# 09_Ethernet.net
KiCad netlist of a schematic drawn in Altium Designer
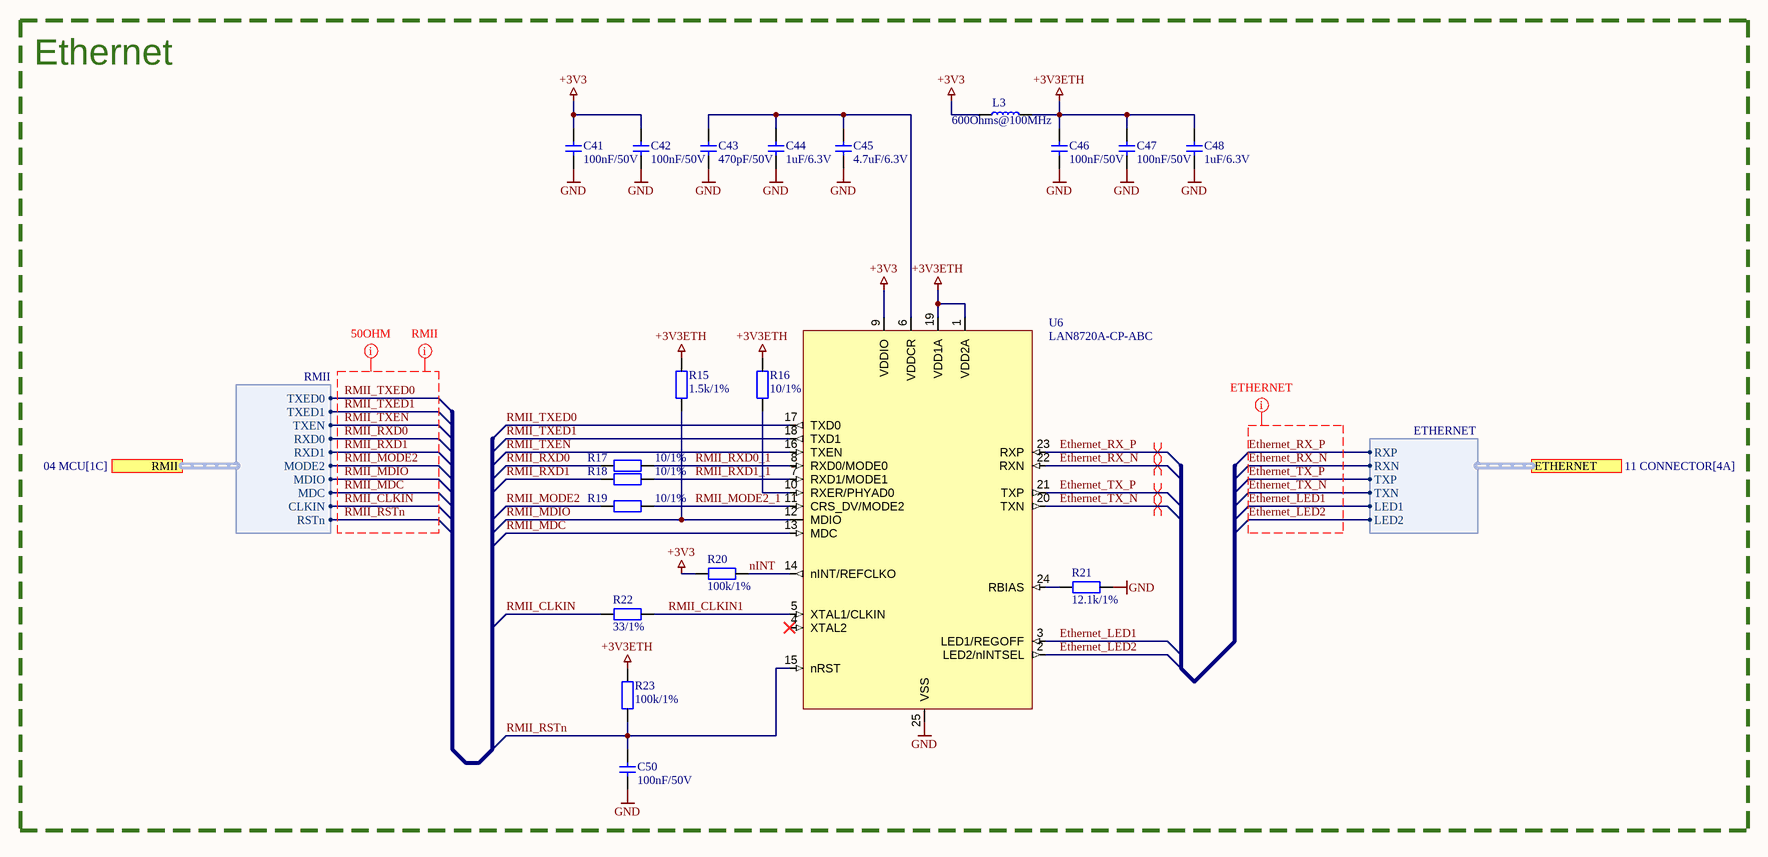
[diagram p0: 09 Ethernet.SchDoc]

(export (version "E")
  (design (tool "Eeschema 10.0.6"))
  (components
    (comp (ref "C41")
      (value "100nF/50V")
      (footprint "CAPC1005X06M-0402")
      (description "0.1 µF ±10% 50V Ceramic Capacitor X7R 0402 (1005 Metric)")
      (fields (field (name "MPN") "GRM155R71H104KE14D"))
      (libsource (lib "Symbol") (part "GRM155R71H104KE14D"))
    )
    (comp (ref "C42")
      (value "100nF/50V")
      (footprint "CAPC1005X06M-0402")
      (description "0.1 µF ±10% 50V Ceramic Capacitor X7R 0402 (1005 Metric)")
      (fields (field (name "MPN") "GRM155R71H104KE14D"))
      (libsource (lib "Symbol") (part "GRM155R71H104KE14D"))
    )
    (comp (ref "C43")
      (value "470pF/50V")
      (footprint "CAPC1005X06M-0402")
      (description "470 pF ±10% 50V Ceramic Capacitor X7R 0402 (1005 Metric)")
      (fields (field (name "MPN") "GRM155R71H471KA01D"))
      (libsource (lib "Symbol") (part "GRM155R71H471KA01D"))
    )
    (comp (ref "C44")
      (value "1uF/6.3V")
      (footprint "CAPC1005X06M-0402")
      (description "1 µF ±10% 6.3V Ceramic Capacitor X7R 0402 (1005 Metric)")
      (fields (field (name "MPN") "GRM155R70J105KA12J"))
      (libsource (lib "Symbol") (part "GRM155R70J105KA12J"))
    )
    (comp (ref "C45")
      (value "4.7uF/6.3V")
      (footprint "CAPC1005X06M-0402")
      (description "4.7 µF ±20% 6.3V Ceramic Capacitor X5R 0402 (1005 Metric)")
      (fields (field (name "MPN") "GRM155R60J475ME47D"))
      (libsource (lib "Symbol") (part "GRM155R60J475ME47D"))
    )
    (comp (ref "C46")
      (value "100nF/50V")
      (footprint "CAPC1005X06M-0402")
      (description "0.1 µF ±10% 50V Ceramic Capacitor X7R 0402 (1005 Metric)")
      (fields (field (name "MPN") "GRM155R71H104KE14D"))
      (libsource (lib "Symbol") (part "GRM155R71H104KE14D"))
    )
    (comp (ref "C47")
      (value "100nF/50V")
      (footprint "CAPC1005X06M-0402")
      (description "0.1 µF ±10% 50V Ceramic Capacitor X7R 0402 (1005 Metric)")
      (fields (field (name "MPN") "GRM155R71H104KE14D"))
      (libsource (lib "Symbol") (part "GRM155R71H104KE14D"))
    )
    (comp (ref "C48")
      (value "1uF/6.3V")
      (footprint "CAPC1005X06M-0402")
      (description "1 µF ±10% 6.3V Ceramic Capacitor X7R 0402 (1005 Metric)")
      (fields (field (name "MPN") "GRM155R70J105KA12J"))
      (libsource (lib "Symbol") (part "GRM155R70J105KA12J"))
    )
    (comp (ref "C50")
      (value "100nF/50V")
      (footprint "CAPC1005X06M-0402")
      (description "0.1 µF ±10% 50V Ceramic Capacitor X7R 0402 (1005 Metric)")
      (fields (field (name "MPN") "GRM155R71H104KE14D"))
      (libsource (lib "Symbol") (part "GRM155R71H104KE14D"))
    )
    (comp (ref "L3")
      (value "600Ohms@100MHz")
      (footprint "INDC1005X06M-0402")
      (description "600 Ohms @ 100 MHz 1 Ferrite Bead 0402 (1005 Metric) 300mA 520mOhm")
      (fields (field (name "MPN") "BLM15AG601SN1D"))
      (libsource (lib "Symbol") (part "BLM15AG601SN1D"))
    )
    (comp (ref "R15")
      (value "1.5k/1%")
      (footprint "RESC1005X04M-0402")
      (description "1.5 kOhms ±1% 0.063W, 1/16W Chip Resistor 0402 (1005 Metric) Moisture Resistant Thick Film")
      (fields (field (name "MPN") "RC0402FR-071K5L"))
      (libsource (lib "Symbol") (part "RC0402FR-071K5L"))
    )
    (comp (ref "R16")
      (value "10/1%")
      (footprint "RESC1005X04M-0402")
      (description "10 Ohms ±1% 0.063W, 1/16W Chip Resistor 0402 (1005 Metric) Moisture Resistant Thick Film")
      (fields (field (name "MPN") "RC0402FR-0710RL"))
      (libsource (lib "Symbol") (part "RC0402FR-0710RL"))
    )
    (comp (ref "R17")
      (value "10/1%")
      (footprint "RESC1005X04M-0402")
      (description "10 Ohms ±1% 0.063W, 1/16W Chip Resistor 0402 (1005 Metric) Moisture Resistant Thick Film")
      (fields (field (name "MPN") "RC0402FR-0710RL"))
      (libsource (lib "Symbol") (part "RC0402FR-0710RL"))
    )
    (comp (ref "R18")
      (value "10/1%")
      (footprint "RESC1005X04M-0402")
      (description "10 Ohms ±1% 0.063W, 1/16W Chip Resistor 0402 (1005 Metric) Moisture Resistant Thick Film")
      (fields (field (name "MPN") "RC0402FR-0710RL"))
      (libsource (lib "Symbol") (part "RC0402FR-0710RL"))
    )
    (comp (ref "R19")
      (value "10/1%")
      (footprint "RESC1005X04M-0402")
      (description "10 Ohms ±1% 0.063W, 1/16W Chip Resistor 0402 (1005 Metric) Moisture Resistant Thick Film")
      (fields (field (name "MPN") "RC0402FR-0710RL"))
      (libsource (lib "Symbol") (part "RC0402FR-0710RL"))
    )
    (comp (ref "R20")
      (value "100k/1%")
      (footprint "RESC1005X04M-0402")
      (description "100 kOhms ±1% 0.063W, 1/16W Chip Resistor 0402 (1005 Metric) Moisture Resistant Thick Film")
      (fields (field (name "MPN") "RC0402FR-07100KL"))
      (libsource (lib "Symbol") (part "RC0402FR-07100KL"))
    )
    (comp (ref "R21")
      (value "12.1k/1%")
      (footprint "RESC1005X04M-0402")
      (description "12.1 kOhms ±1% 0.063W, 1/16W Chip Resistor 0402 (1005 Metric) Moisture Resistant Thick Film")
      (fields (field (name "MPN") "RC0402FR-0712K1L"))
      (libsource (lib "Symbol") (part "RC0402FR-0712K1L"))
    )
    (comp (ref "R22")
      (value "33/1%")
      (footprint "RESC1005X04M-0402")
      (description "33 Ohms ±1% 0.063W, 1/16W Chip Resistor 0402 (1005 Metric) Moisture Resistant Thick Film")
      (fields (field (name "MPN") "RC0402FR-0733RL"))
      (libsource (lib "Symbol") (part "RC0402FR-0733RL"))
    )
    (comp (ref "R23")
      (value "100k/1%")
      (footprint "RESC1005X04M-0402")
      (description "100 kOhms ±1% 0.063W, 1/16W Chip Resistor 0402 (1005 Metric) Moisture Resistant Thick Film")
      (fields (field (name "MPN") "RC0402FR-07100KL"))
      (libsource (lib "Symbol") (part "RC0402FR-07100KL"))
    )
    (comp (ref "U6")
      (value "LAN8720A-CP-ABC")
      (footprint "QFN24P50_40X40X85L40X25")
      (description "2/2 Transceiver Full RMII 24-SQFN (4x4)")
      (libsource (lib "Symbol") (part "LAN8720A"))
    )
  )
  (nets
    (net (code "3") (name "+3V3") (class "Default")
      (node (ref "C41") (pin "2") (pinfunction "2_2") (pintype "passive"))
      (node (ref "C42") (pin "2") (pinfunction "2_2") (pintype "passive"))
      (node (ref "L3") (pin "1") (pinfunction "1_1") (pintype "passive"))
      (node (ref "R20") (pin "1") (pinfunction "1_1") (pintype "passive"))
      (node (ref "U6") (pin "9") (pinfunction "VDDIO_9") (pintype "power_in"))
    )
    (net (code "4") (name "+3V3ETH") (class "Default")
      (node (ref "C46") (pin "2") (pinfunction "2_2") (pintype "passive"))
      (node (ref "C47") (pin "2") (pinfunction "2_2") (pintype "passive"))
      (node (ref "C48") (pin "2") (pinfunction "2_2") (pintype "passive"))
      (node (ref "L3") (pin "2") (pinfunction "2_2") (pintype "passive"))
      (node (ref "R15") (pin "2") (pinfunction "2_2") (pintype "passive"))
      (node (ref "R16") (pin "2") (pinfunction "2_2") (pintype "passive"))
      (node (ref "R23") (pin "1") (pinfunction "1_1") (pintype "passive"))
      (node (ref "U6") (pin "1") (pinfunction "VDD2A_1") (pintype "power_in"))
      (node (ref "U6") (pin "19") (pinfunction "VDD1A_19") (pintype "power_in"))
    )
    (net (code "5") (name "/Ethernet_LED1") (class "Default")
      (node (ref "U6") (pin "3") (pinfunction "LED1/REGOFF_3") (pintype "input"))
    )
    (net (code "6") (name "/Ethernet_LED2") (class "Default")
      (node (ref "U6") (pin "2") (pinfunction "LED2/nINTSEL_2") (pintype "output"))
    )
    (net (code "7") (name "/Ethernet_RX_N") (class "Default")
      (node (ref "U6") (pin "22") (pinfunction "RXN_22") (pintype "input"))
    )
    (net (code "8") (name "/Ethernet_RX_P") (class "Default")
      (node (ref "U6") (pin "23") (pinfunction "RXP_23") (pintype "input"))
    )
    (net (code "9") (name "/Ethernet_TX_N") (class "Default")
      (node (ref "U6") (pin "20") (pinfunction "TXN_20") (pintype "output"))
    )
    (net (code "10") (name "/Ethernet_TX_P") (class "Default")
      (node (ref "U6") (pin "21") (pinfunction "TXP_21") (pintype "output"))
    )
    (net (code "11") (name "/RMII_CLKIN") (class "Default")
      (node (ref "R22") (pin "1") (pinfunction "1_1") (pintype "passive"))
    )
    (net (code "12") (name "/RMII_CLKIN1") (class "Default")
      (node (ref "R22") (pin "2") (pinfunction "2_2") (pintype "passive"))
      (node (ref "U6") (pin "5") (pinfunction "XTAL1/CLKIN_5") (pintype "input"))
    )
    (net (code "13") (name "/RMII_MDC") (class "Default")
      (node (ref "U6") (pin "13") (pinfunction "MDC_13") (pintype "input"))
    )
    (net (code "14") (name "/RMII_MDIO") (class "Default")
      (node (ref "R15") (pin "1") (pinfunction "1_1") (pintype "passive"))
      (node (ref "U6") (pin "12") (pinfunction "MDIO_12") (pintype "bidirectional"))
    )
    (net (code "15") (name "/RMII_MODE2") (class "Default")
      (node (ref "R19") (pin "1") (pinfunction "1_1") (pintype "passive"))
    )
    (net (code "16") (name "/RMII_MODE2_1") (class "Default")
      (node (ref "R19") (pin "2") (pinfunction "2_2") (pintype "passive"))
      (node (ref "U6") (pin "11") (pinfunction "CRS_DV/MODE2_11") (pintype "input"))
    )
    (net (code "17") (name "/RMII_RSTn") (class "Default")
      (node (ref "C50") (pin "2") (pinfunction "2_2") (pintype "passive"))
      (node (ref "R23") (pin "2") (pinfunction "2_2") (pintype "passive"))
      (node (ref "U6") (pin "15") (pinfunction "nRST_15") (pintype "input"))
    )
    (net (code "18") (name "/RMII_RXD0") (class "Default")
      (node (ref "R17") (pin "1") (pinfunction "1_1") (pintype "passive"))
    )
    (net (code "19") (name "/RMII_RXD0_1") (class "Default")
      (node (ref "R17") (pin "2") (pinfunction "2_2") (pintype "passive"))
      (node (ref "U6") (pin "8") (pinfunction "RXD0/MODE0_8") (pintype "input"))
    )
    (net (code "20") (name "/RMII_RXD1") (class "Default")
      (node (ref "R18") (pin "1") (pinfunction "1_1") (pintype "passive"))
    )
    (net (code "21") (name "/RMII_RXD1_1") (class "Default")
      (node (ref "R18") (pin "2") (pinfunction "2_2") (pintype "passive"))
      (node (ref "U6") (pin "7") (pinfunction "RXD1/MODE1_7") (pintype "input"))
    )
    (net (code "22") (name "/RMII_TXED0") (class "Default")
      (node (ref "U6") (pin "17") (pinfunction "TXD0_17") (pintype "output"))
    )
    (net (code "23") (name "/RMII_TXED1") (class "Default")
      (node (ref "U6") (pin "18") (pinfunction "TXD1_18") (pintype "output"))
    )
    (net (code "24") (name "/RMII_TXEN") (class "Default")
      (node (ref "U6") (pin "16") (pinfunction "TXEN_16") (pintype "input"))
    )
    (net (code "25") (name "/nINT") (class "Default")
      (node (ref "R20") (pin "2") (pinfunction "2_2") (pintype "passive"))
      (node (ref "U6") (pin "14") (pinfunction "nINT/REFCLKO_14") (pintype "output"))
    )
    (net (code "28") (name "GND") (class "Default")
      (node (ref "C41") (pin "1") (pinfunction "1_1") (pintype "passive"))
      (node (ref "C42") (pin "1") (pinfunction "1_1") (pintype "passive"))
      (node (ref "C43") (pin "1") (pinfunction "1_1") (pintype "passive"))
      (node (ref "C44") (pin "1") (pinfunction "1_1") (pintype "passive"))
      (node (ref "C45") (pin "1") (pinfunction "1_1") (pintype "passive"))
      (node (ref "C46") (pin "1") (pinfunction "1_1") (pintype "passive"))
      (node (ref "C47") (pin "1") (pinfunction "1_1") (pintype "passive"))
      (node (ref "C48") (pin "1") (pinfunction "1_1") (pintype "passive"))
      (node (ref "C50") (pin "1") (pinfunction "1_1") (pintype "passive"))
      (node (ref "R21") (pin "2") (pinfunction "2_2") (pintype "passive"))
      (node (ref "U6") (pin "25") (pinfunction "VSS_25") (pintype "power_in"))
    )
    (net (code "29") (name "Net-(U6-RBIAS)") (class "Default")
      (node (ref "R21") (pin "1") (pinfunction "1_1") (pintype "passive"))
      (node (ref "U6") (pin "24") (pinfunction "RBIAS_24") (pintype "input"))
    )
    (net (code "30") (name "Net-(U6-RXER{slash}PHYAD0)") (class "Default")
      (node (ref "R16") (pin "1") (pinfunction "1_1") (pintype "passive"))
      (node (ref "U6") (pin "10") (pinfunction "RXER/PHYAD0_10") (pintype "input"))
    )
    (net (code "31") (name "Net-(U6-VDDCR)") (class "Default")
      (node (ref "C43") (pin "2") (pinfunction "2_2") (pintype "passive"))
      (node (ref "C44") (pin "2") (pinfunction "2_2") (pintype "passive"))
      (node (ref "C45") (pin "2") (pinfunction "2_2") (pintype "passive"))
      (node (ref "U6") (pin "6") (pinfunction "VDDCR_6") (pintype "power_in"))
    )
    (net (code "32") (name "unconnected-(U6-XTAL2-Pad4)") (class "Default")
      (node (ref "U6") (pin "4") (pinfunction "XTAL2_4") (pintype "input+no_connect"))
    )
  )
)
